# Qwiic_PL-N823_IR_Breakout.net
KiCad netlist of a schematic drawn in EAGLE
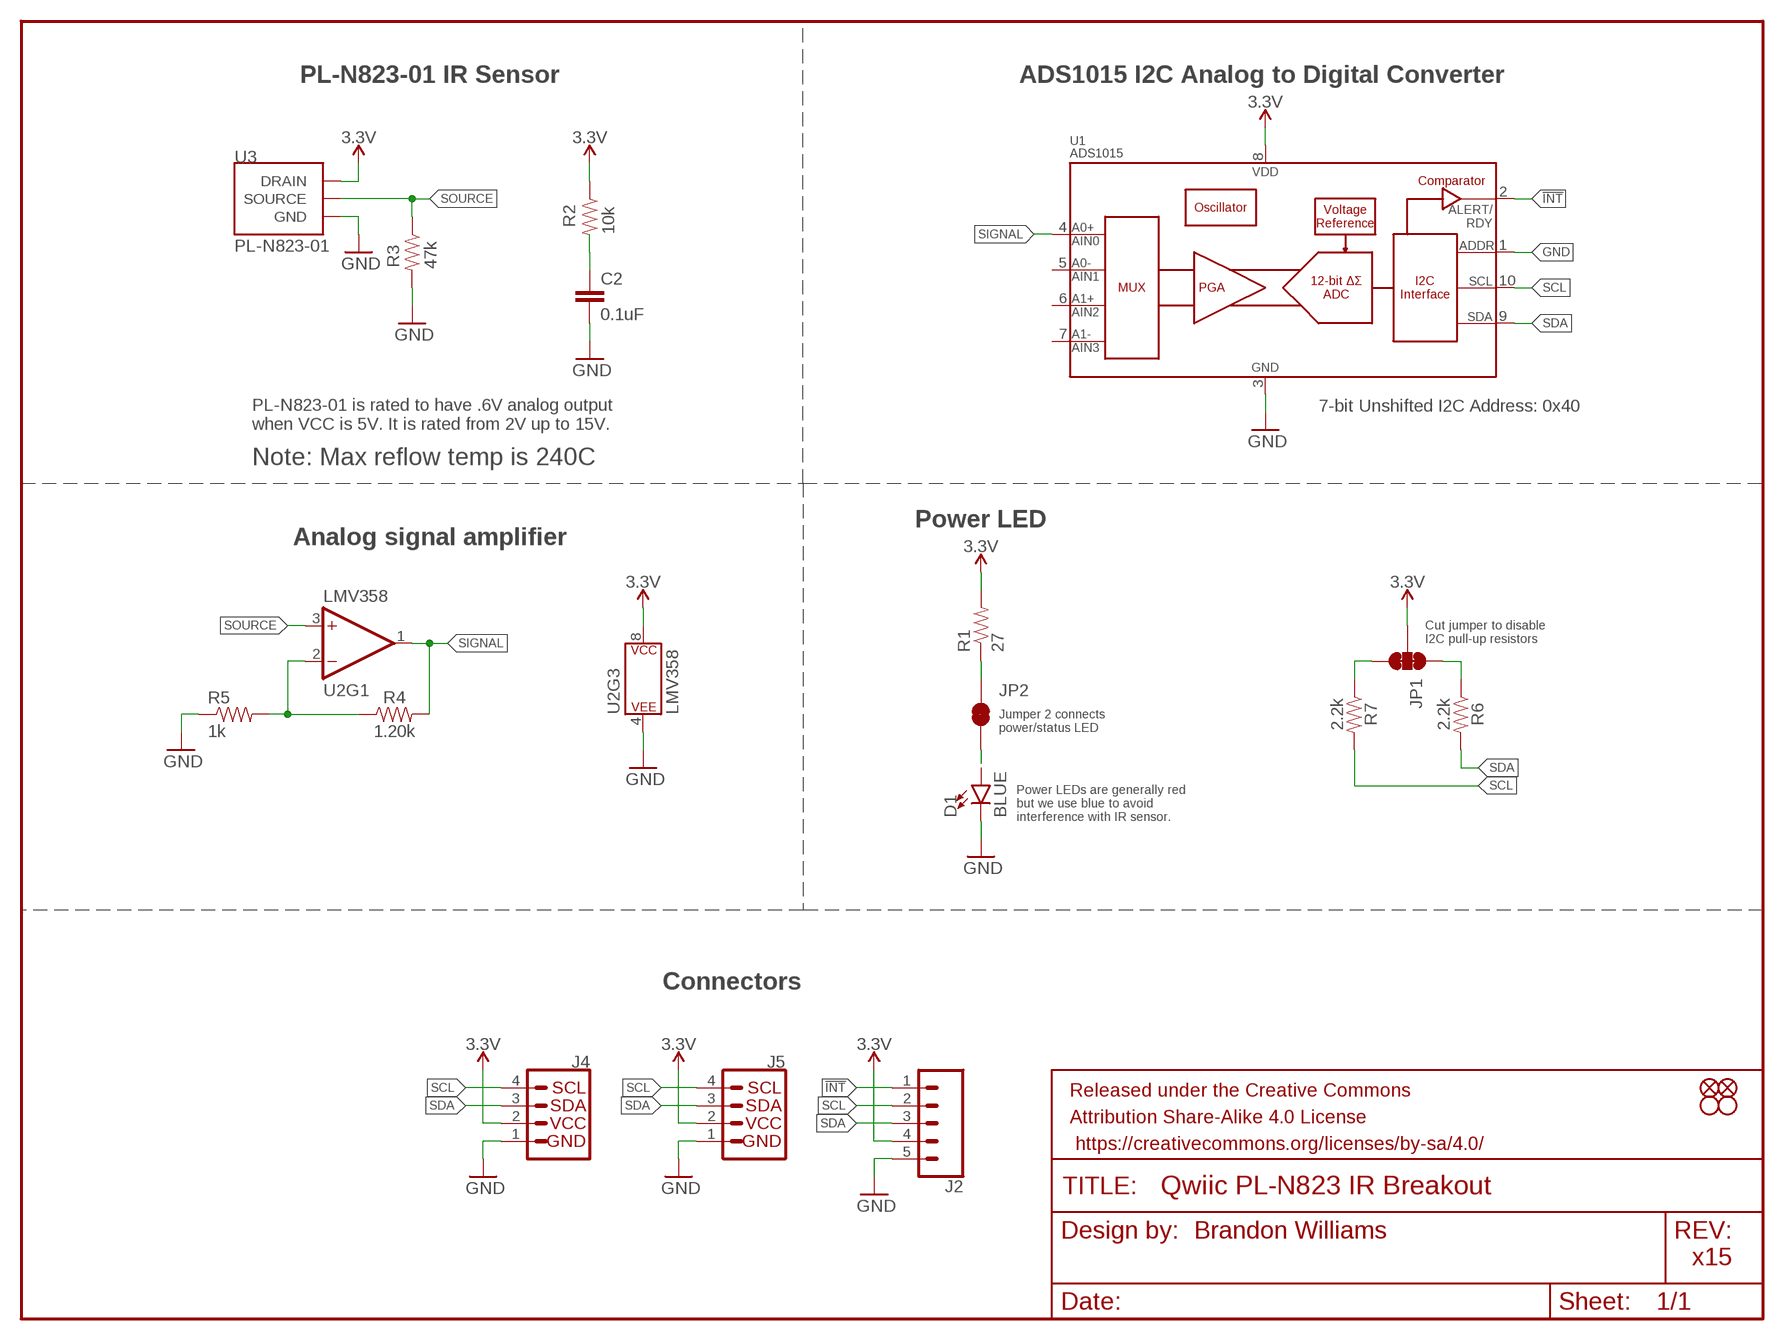
[diagram p0: schematic, sheet 1]

(export (version "E")
  (design (tool "Eeschema 10.0.6"))
  (components
    (comp (ref "C2")
      (value "0.1uF")
      (footprint "eagle-import:0603")
      (libsource (lib "eagle-import") (part "0.1UF-0603-25V-(+80/-20%)"))
    )
    (comp (ref "D1")
      (value "BLUE")
      (footprint "eagle-import:LED-0603")
      (libsource (lib "eagle-import") (part "LED-BLUE0603"))
    )
    (comp (ref "FD1")
      (value "FIDUCIALUFIDUCIAL")
      (footprint "eagle-import:FIDUCIAL-MICRO")
      (libsource (lib "eagle-import") (part "FIDUCIALUFIDUCIAL"))
    )
    (comp (ref "FD2")
      (value "FIDUCIALUFIDUCIAL")
      (footprint "eagle-import:FIDUCIAL-MICRO")
      (libsource (lib "eagle-import") (part "FIDUCIALUFIDUCIAL"))
    )
    (comp (ref "FRAME1")
      (value "FRAME-LETTERNO_PACKAGE")
      (footprint "eagle-import:DUMMY")
      (fields (field (name "DESIGNER") "Nobody"))
      (libsource (lib "eagle-import") (part "FRAME-LETTERNO_PACKAGE"))
    )
    (comp (ref "H1")
      (value "STAND-OFFTIGHT")
      (footprint "eagle-import:STAND-OFF-TIGHT")
      (libsource (lib "eagle-import") (part "STAND-OFFTIGHT"))
    )
    (comp (ref "H2")
      (value "STAND-OFFTIGHT")
      (footprint "eagle-import:STAND-OFF-TIGHT")
      (libsource (lib "eagle-import") (part "STAND-OFFTIGHT"))
    )
    (comp (ref "J2")
      (value "CONN_05NO_SILK")
      (footprint "eagle-import:1X05_NO_SILK")
      (libsource (lib "eagle-import") (part "CONN_05NO_SILK"))
    )
    (comp (ref "J4")
      (value "QWIIC_CONNECTORJS-1MM")
      (footprint "eagle-import:JST04_1MM_RA")
      (libsource (lib "eagle-import") (part "QWIIC_CONNECTORJS-1MM"))
    )
    (comp (ref "J5")
      (value "QWIIC_CONNECTORJS-1MM")
      (footprint "eagle-import:JST04_1MM_RA")
      (libsource (lib "eagle-import") (part "QWIIC_CONNECTORJS-1MM"))
    )
    (comp (ref "JP1")
      (value "JUMPER-SMT_3_2-NC_TRACE_SILK")
      (footprint "eagle-import:SMT-JUMPER_3_2-NC_TRACE_SILK")
      (libsource (lib "eagle-import") (part "JUMPER-SMT_3_2-NC_TRACE_SILK"))
    )
    (comp (ref "JP2")
      (value "JUMPER-SMT_2_NC_TRACE_SILK")
      (footprint "eagle-import:SMT-JUMPER_2_NC_TRACE_SILK")
      (libsource (lib "eagle-import") (part "JUMPER-SMT_2_NC_TRACE_SILK"))
    )
    (comp (ref "R1")
      (value "27")
      (footprint "eagle-import:0603")
      (libsource (lib "eagle-import") (part "27OHM-0603-1/10W-1%"))
    )
    (comp (ref "R2")
      (value "10k")
      (footprint "eagle-import:0603")
      (libsource (lib "eagle-import") (part "10KOHM-0603-1/10W-1%"))
    )
    (comp (ref "R3")
      (value "47k")
      (footprint "eagle-import:0603")
      (libsource (lib "eagle-import") (part "47KOHM-0603-1/10W-1%"))
    )
    (comp (ref "R4")
      (value "1.20k")
      (footprint "eagle-import:0603")
      (libsource (lib "eagle-import") (part "1.20KOHM-0603-1/10W-1%"))
    )
    (comp (ref "R5")
      (value "1k")
      (footprint "eagle-import:0603")
      (libsource (lib "eagle-import") (part "1KOHM-0603-1/10W-1%"))
    )
    (comp (ref "R6")
      (value "2.2k")
      (footprint "eagle-import:0603")
      (libsource (lib "eagle-import") (part "2.2KOHM-0603-1/10W-1%"))
    )
    (comp (ref "R7")
      (value "2.2k")
      (footprint "eagle-import:0603")
      (libsource (lib "eagle-import") (part "2.2KOHM-0603-1/10W-1%"))
    )
    (comp (ref "U1")
      (value "ADS1015")
      (footprint "eagle-import:MSOP10")
      (libsource (lib "eagle-import") (part "ADS1015"))
    )
    (comp (ref "U2")
      (value "LMV358")
      (footprint "eagle-import:SO08")
      (libsource (lib "eagle-import") (part "LMV358SOIC"))
    )
    (comp (ref "U3")
      (value "PL-N823-01")
      (footprint "eagle-import:PL-N823-01")
      (libsource (lib "eagle-import") (part "PL-N823-01"))
    )
  )
  (nets
    (net (code "1") (name "/~{INT}") (class "Default")
      (node (ref "J2") (pin "1") (pinfunction "1_1") (pintype "passive"))
      (node (ref "U1") (pin "2") (pinfunction "ALERT/RDY_2") (pintype "bidirectional"))
    )
    (net (code "2") (name "3.3V") (class "Default")
      (node (ref "J2") (pin "4") (pinfunction "4_4") (pintype "passive"))
      (node (ref "J4") (pin "2") (pinfunction "2_2") (pintype "power_in"))
      (node (ref "J5") (pin "2") (pinfunction "2_2") (pintype "power_in"))
      (node (ref "JP1") (pin "2") (pinfunction "2_2") (pintype "passive"))
      (node (ref "R1") (pin "2") (pinfunction "2_2") (pintype "passive"))
      (node (ref "R2") (pin "1") (pinfunction "1_1") (pintype "passive"))
      (node (ref "U1") (pin "8") (pinfunction "VDD_8") (pintype "bidirectional"))
      (node (ref "U2") (pin "8") (pinfunction "P$V+_8") (pintype "bidirectional"))
      (node (ref "U3") (pin "DRAIN") (pinfunction "DRAIN_DRAIN") (pintype "input"))
    )
    (net (code "3") (name "GND") (class "Default")
      (node (ref "C2") (pin "2") (pinfunction "2_2") (pintype "passive"))
      (node (ref "D1") (pin "C") (pinfunction "C_C") (pintype "passive"))
      (node (ref "J2") (pin "5") (pinfunction "5_5") (pintype "passive"))
      (node (ref "J4") (pin "1") (pinfunction "1_1") (pintype "power_in"))
      (node (ref "J5") (pin "1") (pinfunction "1_1") (pintype "power_in"))
      (node (ref "R3") (pin "2") (pinfunction "2_2") (pintype "passive"))
      (node (ref "R5") (pin "1") (pinfunction "1_1") (pintype "passive"))
      (node (ref "U1") (pin "1") (pinfunction "ADDR_1") (pintype "bidirectional"))
      (node (ref "U1") (pin "3") (pinfunction "VSS_3") (pintype "bidirectional"))
      (node (ref "U2") (pin "4") (pinfunction "P$V-_4") (pintype "bidirectional"))
      (node (ref "U3") (pin "GND@1") (pinfunction "GND_GND@1") (pintype "power_in"))
      (node (ref "U3") (pin "GND@2") (pinfunction "GND_GND@2") (pintype "power_in"))
    )
    (net (code "4") (name "Net-(C2-Pad1)") (class "Default")
      (node (ref "C2") (pin "1") (pinfunction "1_1") (pintype "passive"))
      (node (ref "R2") (pin "2") (pinfunction "2_2") (pintype "passive"))
    )
    (net (code "5") (name "Net-(D1-PadA)") (class "Default")
      (node (ref "D1") (pin "A") (pinfunction "A_A") (pintype "passive"))
      (node (ref "JP2") (pin "2") (pinfunction "2_2") (pintype "passive"))
    )
    (net (code "6") (name "Net-(JP1-Pad1)") (class "Default")
      (node (ref "JP1") (pin "1") (pinfunction "1_1") (pintype "passive"))
      (node (ref "R6") (pin "1") (pinfunction "1_1") (pintype "passive"))
    )
    (net (code "7") (name "Net-(JP1-Pad3)") (class "Default")
      (node (ref "JP1") (pin "3") (pinfunction "3_3") (pintype "passive"))
      (node (ref "R7") (pin "1") (pinfunction "1_1") (pintype "passive"))
    )
    (net (code "8") (name "Net-(JP2-Pad1)") (class "Default")
      (node (ref "JP2") (pin "1") (pinfunction "1_1") (pintype "passive"))
      (node (ref "R1") (pin "1") (pinfunction "1_1") (pintype "passive"))
    )
    (net (code "9") (name "Net-(U2A--IN)") (class "Default")
      (node (ref "R4") (pin "1") (pinfunction "1_1") (pintype "passive"))
      (node (ref "R5") (pin "2") (pinfunction "2_2") (pintype "passive"))
      (node (ref "U2") (pin "2") (pinfunction "-IN_2") (pintype "input"))
    )
    (net (code "10") (name "SCL") (class "Default")
      (node (ref "J2") (pin "2") (pinfunction "2_2") (pintype "passive"))
      (node (ref "J4") (pin "4") (pinfunction "4_4") (pintype "passive"))
      (node (ref "J5") (pin "4") (pinfunction "4_4") (pintype "passive"))
      (node (ref "R7") (pin "2") (pinfunction "2_2") (pintype "passive"))
      (node (ref "U1") (pin "10") (pinfunction "SCL_10") (pintype "bidirectional"))
    )
    (net (code "11") (name "SDA") (class "Default")
      (node (ref "J2") (pin "3") (pinfunction "3_3") (pintype "passive"))
      (node (ref "J4") (pin "3") (pinfunction "3_3") (pintype "passive"))
      (node (ref "J5") (pin "3") (pinfunction "3_3") (pintype "passive"))
      (node (ref "R6") (pin "2") (pinfunction "2_2") (pintype "passive"))
      (node (ref "U1") (pin "9") (pinfunction "SDA_9") (pintype "bidirectional"))
    )
    (net (code "12") (name "SIGNAL") (class "Default")
      (node (ref "R4") (pin "2") (pinfunction "2_2") (pintype "passive"))
      (node (ref "U1") (pin "4") (pinfunction "AIN0_4") (pintype "bidirectional"))
      (node (ref "U2") (pin "1") (pinfunction "OUT_1") (pintype "output"))
    )
    (net (code "13") (name "SOURCE") (class "Default")
      (node (ref "R3") (pin "1") (pinfunction "1_1") (pintype "passive"))
      (node (ref "U2") (pin "3") (pinfunction "+IN_3") (pintype "input"))
      (node (ref "U3") (pin "SOURCE") (pinfunction "SOURCE_SOURCE") (pintype "output"))
    )
    (net (code "14") (name "unconnected-(U1-AIN1-Pad5)") (class "Default")
      (node (ref "U1") (pin "5") (pinfunction "AIN1_5") (pintype "bidirectional"))
    )
    (net (code "15") (name "unconnected-(U1-AIN2-Pad6)") (class "Default")
      (node (ref "U1") (pin "6") (pinfunction "AIN2_6") (pintype "bidirectional"))
    )
    (net (code "16") (name "unconnected-(U1-AIN3-Pad7)") (class "Default")
      (node (ref "U1") (pin "7") (pinfunction "AIN3_7") (pintype "bidirectional"))
    )
  )
)
